# arduinosnull.net
KiCad netlist of a schematic drawn in EAGLE
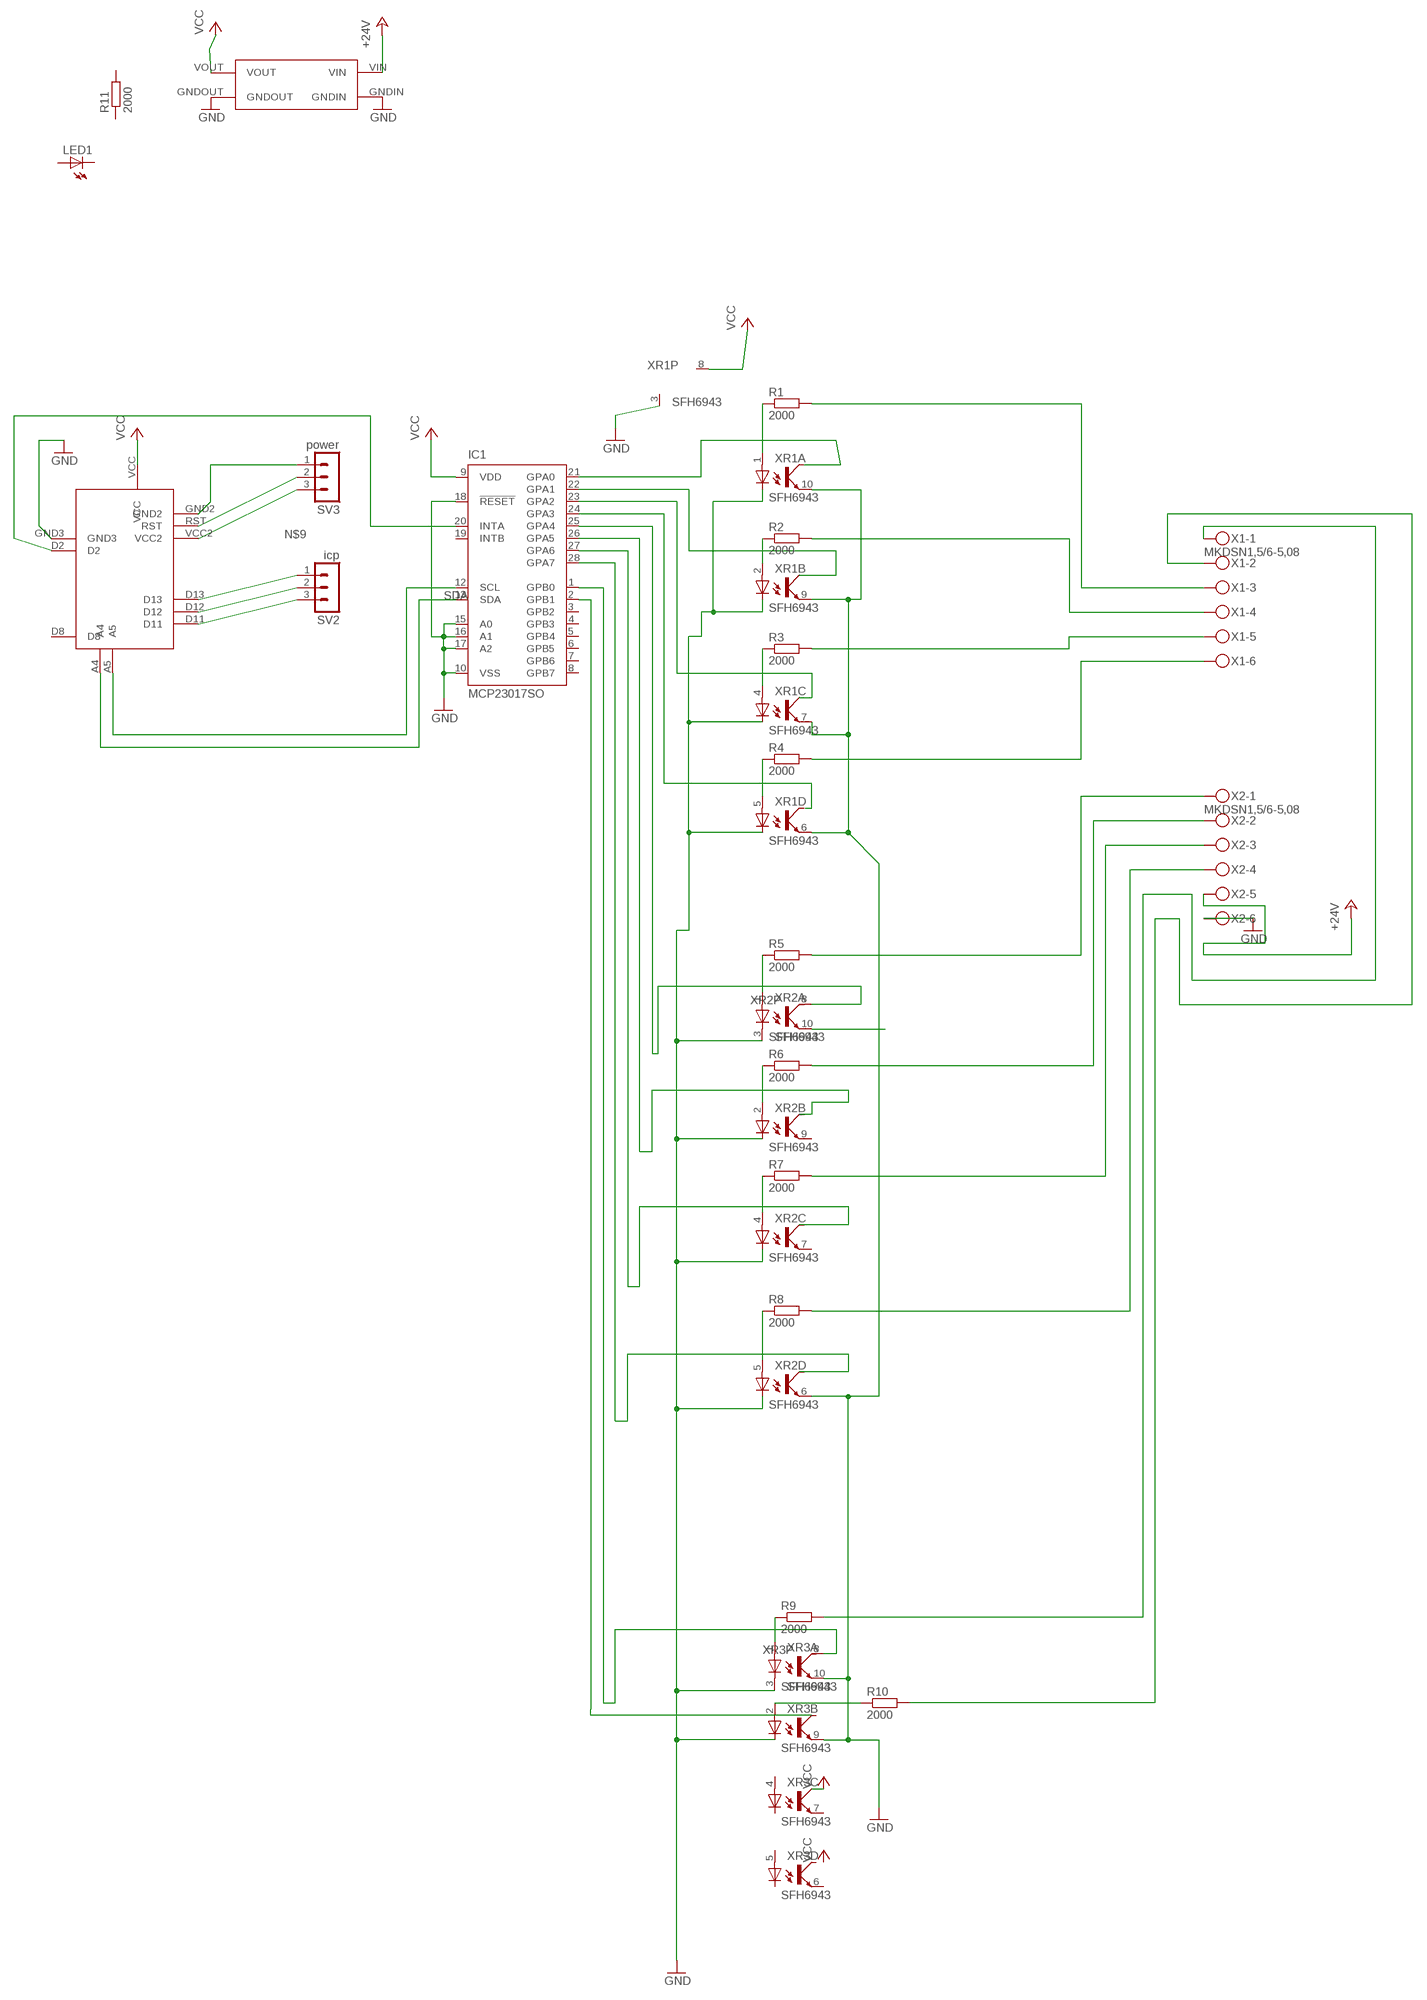
[diagram p0: schematic, sheet 1]

(export (version "E")
  (design (tool "Eeschema 10.0.6"))
  (components
    (comp (ref "IC1")
      (value "MCP23017SO")
      (footprint "eagle-import:SO28W")
      (fields (field (name "MF") "MICROCHIP") (field (name "MPN") "MCP23017-E/SO"))
      (libsource (lib "eagle-import") (part "MCP23017SO"))
    )
    (comp (ref "LED1")
      (value "LEDSML0805")
      (footprint "eagle-import:SML0805")
      (libsource (lib "eagle-import") (part "LEDSML0805"))
    )
    (comp (ref "R1")
      (value "2000")
      (footprint "eagle-import:M0805")
      (libsource (lib "eagle-import") (part "R-EU_M0805"))
    )
    (comp (ref "R2")
      (value "2000")
      (footprint "eagle-import:M0805")
      (libsource (lib "eagle-import") (part "R-EU_M0805"))
    )
    (comp (ref "R3")
      (value "2000")
      (footprint "eagle-import:M0805")
      (libsource (lib "eagle-import") (part "R-EU_M0805"))
    )
    (comp (ref "R4")
      (value "2000")
      (footprint "eagle-import:M0805")
      (libsource (lib "eagle-import") (part "R-EU_M0805"))
    )
    (comp (ref "R5")
      (value "2000")
      (footprint "eagle-import:M0805")
      (libsource (lib "eagle-import") (part "R-EU_M0805"))
    )
    (comp (ref "R6")
      (value "2000")
      (footprint "eagle-import:M0805")
      (libsource (lib "eagle-import") (part "R-EU_M0805"))
    )
    (comp (ref "R7")
      (value "2000")
      (footprint "eagle-import:M0805")
      (libsource (lib "eagle-import") (part "R-EU_M0805"))
    )
    (comp (ref "R8")
      (value "2000")
      (footprint "eagle-import:M0805")
      (libsource (lib "eagle-import") (part "R-EU_M0805"))
    )
    (comp (ref "R9")
      (value "2000")
      (footprint "eagle-import:M0805")
      (libsource (lib "eagle-import") (part "R-EU_M0805"))
    )
    (comp (ref "R10")
      (value "2000")
      (footprint "eagle-import:M0805")
      (libsource (lib "eagle-import") (part "R-EU_M0805"))
    )
    (comp (ref "R11")
      (value "2000")
      (footprint "eagle-import:M0805")
      (libsource (lib "eagle-import") (part "R-EU_M0805"))
    )
    (comp (ref "SV2")
      (value "icp")
      (footprint "eagle-import:MA03-1")
      (libsource (lib "eagle-import") (part "MA03-1"))
    )
    (comp (ref "SV3")
      (value "power")
      (footprint "eagle-import:MA03-1")
      (libsource (lib "eagle-import") (part "MA03-1"))
    )
    (comp (ref "U$1")
      (value "ARDUINOPROMINIREDUCED")
      (footprint "eagle-import:ARDUINOPROMINIREDUCED")
      (libsource (lib "eagle-import") (part "ARDUINOPROMINIREDUCED"))
    )
    (comp (ref "U$2")
      (value "VREGMODULE")
      (footprint "eagle-import:VREGMODULE")
      (libsource (lib "eagle-import") (part "VREGMODULE"))
    )
    (comp (ref "X1")
      (value "MKDSN1,5/6-5,08")
      (footprint "eagle-import:MKDSN1,5_6-5,08")
      (libsource (lib "eagle-import") (part "MKDSN1,5/6-5,08"))
    )
    (comp (ref "X2")
      (value "MKDSN1,5/6-5,08")
      (footprint "eagle-import:MKDSN1,5_6-5,08")
      (libsource (lib "eagle-import") (part "MKDSN1,5/6-5,08"))
    )
    (comp (ref "XR1")
      (value "SFH6943")
      (footprint "eagle-import:SOT223_10")
      (fields (field (name "MPN") "SFH6943A-4T"))
      (libsource (lib "eagle-import") (part "SFH6943"))
    )
    (comp (ref "XR2")
      (value "SFH6943")
      (footprint "eagle-import:SOT223_10")
      (fields (field (name "MPN") "SFH6943A-4T"))
      (libsource (lib "eagle-import") (part "SFH6943"))
    )
    (comp (ref "XR3")
      (value "SFH6943")
      (footprint "eagle-import:SOT223_10")
      (fields (field (name "MPN") "SFH6943A-4T"))
      (libsource (lib "eagle-import") (part "SFH6943"))
    )
  )
  (nets
    (net (code "1") (name "+24V") (class "Default")
      (node (ref "U$2") (pin "VIN") (pinfunction "VIN_VIN") (pintype "bidirectional"))
      (node (ref "X2") (pin "5") (pinfunction "KL_5") (pintype "passive"))
    )
    (net (code "2") (name "/N$9") (class "Default")
      (node (ref "SV3") (pin "3") (pinfunction "3_3") (pintype "passive"))
      (node (ref "U$1") (pin "VCC2") (pinfunction "VCC2_VCC2") (pintype "bidirectional"))
    )
    (net (code "3") (name "/SDA") (class "Default")
      (node (ref "IC1") (pin "13") (pinfunction "SDA_13") (pintype "bidirectional"))
      (node (ref "U$1") (pin "A4") (pinfunction "A4_A4") (pintype "bidirectional"))
    )
    (net (code "4") (name "GND") (class "Default")
      (node (ref "IC1") (pin "10") (pinfunction "VSS_10") (pintype "power_in"))
      (node (ref "IC1") (pin "15") (pinfunction "A0_15") (pintype "input"))
      (node (ref "IC1") (pin "16") (pinfunction "A1_16") (pintype "input"))
      (node (ref "IC1") (pin "17") (pinfunction "A2_17") (pintype "input"))
      (node (ref "IC1") (pin "18") (pinfunction "~{RESET}_18") (pintype "input"))
      (node (ref "U$1") (pin "GND3") (pinfunction "GND3_GND3") (pintype "bidirectional"))
      (node (ref "U$2") (pin "GNDIN") (pinfunction "GNDIN_GNDIN") (pintype "bidirectional"))
      (node (ref "U$2") (pin "GNDOUT") (pinfunction "GNDOUT_GNDOUT") (pintype "bidirectional"))
      (node (ref "X2") (pin "6") (pinfunction "KL_6") (pintype "passive"))
      (node (ref "XR1") (pin "10") (pinfunction "EMI_10") (pintype "passive"))
      (node (ref "XR1") (pin "3") (pinfunction "COM-CAT_3") (pintype "passive"))
      (node (ref "XR1") (pin "6") (pinfunction "EMI_6") (pintype "passive"))
      (node (ref "XR1") (pin "7") (pinfunction "EMI_7") (pintype "passive"))
      (node (ref "XR1") (pin "9") (pinfunction "EMI_9") (pintype "passive"))
      (node (ref "XR2") (pin "3") (pinfunction "COM-CAT_3") (pintype "passive"))
      (node (ref "XR2") (pin "6") (pinfunction "EMI_6") (pintype "passive"))
      (node (ref "XR3") (pin "10") (pinfunction "EMI_10") (pintype "passive"))
      (node (ref "XR3") (pin "3") (pinfunction "COM-CAT_3") (pintype "passive"))
      (node (ref "XR3") (pin "9") (pinfunction "EMI_9") (pintype "passive"))
    )
    (net (code "5") (name "Net-(IC1-GPA4)") (class "Default")
      (node (ref "IC1") (pin "25") (pinfunction "GPA4_25") (pintype "bidirectional"))
      (node (ref "XR2") (pin "8") (pinfunction "COM-COL_8") (pintype "passive"))
    )
    (net (code "6") (name "Net-(IC1-GPB0)") (class "Default")
      (node (ref "IC1") (pin "1") (pinfunction "GPB0_1") (pintype "bidirectional"))
      (node (ref "XR3") (pin "8") (pinfunction "COM-COL_8") (pintype "passive"))
    )
    (net (code "7") (name "Net-(IC1-INTA)") (class "Default")
      (node (ref "IC1") (pin "20") (pinfunction "INTA_20") (pintype "output"))
      (node (ref "U$1") (pin "D2") (pinfunction "D2_D2") (pintype "bidirectional"))
    )
    (net (code "8") (name "Net-(IC1-SCL)") (class "Default")
      (node (ref "IC1") (pin "12") (pinfunction "SCL_12") (pintype "input"))
      (node (ref "U$1") (pin "A5") (pinfunction "A5_A5") (pintype "bidirectional"))
    )
    (net (code "9") (name "Net-(SV2-Pad1)") (class "Default")
      (node (ref "SV2") (pin "1") (pinfunction "1_1") (pintype "passive"))
      (node (ref "U$1") (pin "D13") (pinfunction "D13_D13") (pintype "bidirectional"))
    )
    (net (code "10") (name "Net-(SV2-Pad2)") (class "Default")
      (node (ref "SV2") (pin "2") (pinfunction "2_2") (pintype "passive"))
      (node (ref "U$1") (pin "D12") (pinfunction "D12_D12") (pintype "bidirectional"))
    )
    (net (code "11") (name "Net-(SV2-Pad3)") (class "Default")
      (node (ref "SV2") (pin "3") (pinfunction "3_3") (pintype "passive"))
      (node (ref "U$1") (pin "D11") (pinfunction "D11_D11") (pintype "bidirectional"))
    )
    (net (code "12") (name "Net-(SV3-Pad1)") (class "Default")
      (node (ref "SV3") (pin "1") (pinfunction "1_1") (pintype "passive"))
      (node (ref "U$1") (pin "GND2") (pinfunction "GND2_GND2") (pintype "bidirectional"))
    )
    (net (code "13") (name "Net-(SV3-Pad2)") (class "Default")
      (node (ref "SV3") (pin "2") (pinfunction "2_2") (pintype "passive"))
      (node (ref "U$1") (pin "RST") (pinfunction "RST_RST") (pintype "bidirectional"))
    )
    (net (code "14") (name "Net-(X1A-KL)") (class "Default")
      (node (ref "R9") (pin "2") (pinfunction "2_2") (pintype "passive"))
      (node (ref "X1") (pin "1") (pinfunction "KL_1") (pintype "passive"))
    )
    (net (code "15") (name "Net-(X1B-KL)") (class "Default")
      (node (ref "R10") (pin "2") (pinfunction "2_2") (pintype "passive"))
      (node (ref "X1") (pin "2") (pinfunction "KL_2") (pintype "passive"))
    )
    (net (code "16") (name "Net-(X1C-KL)") (class "Default")
      (node (ref "R1") (pin "2") (pinfunction "2_2") (pintype "passive"))
      (node (ref "X1") (pin "3") (pinfunction "KL_3") (pintype "passive"))
    )
    (net (code "17") (name "Net-(X1D-KL)") (class "Default")
      (node (ref "R2") (pin "2") (pinfunction "2_2") (pintype "passive"))
      (node (ref "X1") (pin "4") (pinfunction "KL_4") (pintype "passive"))
    )
    (net (code "18") (name "Net-(X1E-KL)") (class "Default")
      (node (ref "R3") (pin "2") (pinfunction "2_2") (pintype "passive"))
      (node (ref "X1") (pin "5") (pinfunction "KL_5") (pintype "passive"))
    )
    (net (code "19") (name "Net-(X1F-KL)") (class "Default")
      (node (ref "R4") (pin "2") (pinfunction "2_2") (pintype "passive"))
      (node (ref "X1") (pin "6") (pinfunction "KL_6") (pintype "passive"))
    )
    (net (code "20") (name "Net-(X2A-KL)") (class "Default")
      (node (ref "R5") (pin "2") (pinfunction "2_2") (pintype "passive"))
      (node (ref "X2") (pin "1") (pinfunction "KL_1") (pintype "passive"))
    )
    (net (code "21") (name "Net-(X2B-KL)") (class "Default")
      (node (ref "R6") (pin "2") (pinfunction "2_2") (pintype "passive"))
      (node (ref "X2") (pin "2") (pinfunction "KL_2") (pintype "passive"))
    )
    (net (code "22") (name "Net-(X2C-KL)") (class "Default")
      (node (ref "R7") (pin "2") (pinfunction "2_2") (pintype "passive"))
      (node (ref "X2") (pin "3") (pinfunction "KL_3") (pintype "passive"))
    )
    (net (code "23") (name "Net-(X2D-KL)") (class "Default")
      (node (ref "R8") (pin "2") (pinfunction "2_2") (pintype "passive"))
      (node (ref "X2") (pin "4") (pinfunction "KL_4") (pintype "passive"))
    )
    (net (code "24") (name "Net-(XR1A-A)") (class "Default")
      (node (ref "R1") (pin "1") (pinfunction "1_1") (pintype "passive"))
      (node (ref "XR1") (pin "1") (pinfunction "A_1") (pintype "passive"))
    )
    (net (code "25") (name "Net-(XR1B-A)") (class "Default")
      (node (ref "R2") (pin "1") (pinfunction "1_1") (pintype "passive"))
      (node (ref "XR1") (pin "2") (pinfunction "A_2") (pintype "passive"))
    )
    (net (code "26") (name "Net-(XR1C-A)") (class "Default")
      (node (ref "R3") (pin "1") (pinfunction "1_1") (pintype "passive"))
      (node (ref "XR1") (pin "4") (pinfunction "A_4") (pintype "passive"))
    )
    (net (code "27") (name "Net-(XR1D-A)") (class "Default")
      (node (ref "R4") (pin "1") (pinfunction "1_1") (pintype "passive"))
      (node (ref "XR1") (pin "5") (pinfunction "A_5") (pintype "passive"))
    )
    (net (code "28") (name "Net-(XR2A-A)") (class "Default")
      (node (ref "R5") (pin "1") (pinfunction "1_1") (pintype "passive"))
      (node (ref "XR2") (pin "1") (pinfunction "A_1") (pintype "passive"))
    )
    (net (code "29") (name "Net-(XR2B-A)") (class "Default")
      (node (ref "R6") (pin "1") (pinfunction "1_1") (pintype "passive"))
      (node (ref "XR2") (pin "2") (pinfunction "A_2") (pintype "passive"))
    )
    (net (code "30") (name "Net-(XR2C-A)") (class "Default")
      (node (ref "R7") (pin "1") (pinfunction "1_1") (pintype "passive"))
      (node (ref "XR2") (pin "4") (pinfunction "A_4") (pintype "passive"))
    )
    (net (code "31") (name "Net-(XR2D-A)") (class "Default")
      (node (ref "R8") (pin "1") (pinfunction "1_1") (pintype "passive"))
      (node (ref "XR2") (pin "5") (pinfunction "A_5") (pintype "passive"))
    )
    (net (code "32") (name "Net-(XR3A-A)") (class "Default")
      (node (ref "R9") (pin "1") (pinfunction "1_1") (pintype "passive"))
      (node (ref "XR3") (pin "1") (pinfunction "A_1") (pintype "passive"))
    )
    (net (code "33") (name "Net-(XR3B-A)") (class "Default")
      (node (ref "R10") (pin "1") (pinfunction "1_1") (pintype "passive"))
      (node (ref "XR3") (pin "2") (pinfunction "A_2") (pintype "passive"))
    )
    (net (code "34") (name "VCC") (class "Default")
      (node (ref "IC1") (pin "9") (pinfunction "VDD_9") (pintype "power_in"))
      (node (ref "U$1") (pin "VCC") (pinfunction "VCC_VCC") (pintype "bidirectional"))
      (node (ref "U$2") (pin "VOUT") (pinfunction "VOUT_VOUT") (pintype "bidirectional"))
      (node (ref "XR1") (pin "8") (pinfunction "COM-COL_8") (pintype "passive"))
    )
    (net (code "35") (name "unconnected-(IC1-GPA0-Pad21)") (class "Default")
      (node (ref "IC1") (pin "21") (pinfunction "GPA0_21") (pintype "bidirectional"))
    )
    (net (code "36") (name "unconnected-(IC1-GPA1-Pad22)") (class "Default")
      (node (ref "IC1") (pin "22") (pinfunction "GPA1_22") (pintype "bidirectional"))
    )
    (net (code "37") (name "unconnected-(IC1-GPA2-Pad23)") (class "Default")
      (node (ref "IC1") (pin "23") (pinfunction "GPA2_23") (pintype "bidirectional"))
    )
    (net (code "38") (name "unconnected-(IC1-GPA3-Pad24)") (class "Default")
      (node (ref "IC1") (pin "24") (pinfunction "GPA3_24") (pintype "bidirectional"))
    )
    (net (code "39") (name "unconnected-(IC1-GPA5-Pad26)") (class "Default")
      (node (ref "IC1") (pin "26") (pinfunction "GPA5_26") (pintype "bidirectional"))
    )
    (net (code "40") (name "unconnected-(IC1-GPA6-Pad27)") (class "Default")
      (node (ref "IC1") (pin "27") (pinfunction "GPA6_27") (pintype "bidirectional"))
    )
    (net (code "41") (name "unconnected-(IC1-GPA7-Pad28)") (class "Default")
      (node (ref "IC1") (pin "28") (pinfunction "GPA7_28") (pintype "bidirectional"))
    )
    (net (code "42") (name "unconnected-(IC1-GPB1-Pad2)") (class "Default")
      (node (ref "IC1") (pin "2") (pinfunction "GPB1_2") (pintype "bidirectional"))
    )
    (net (code "43") (name "unconnected-(IC1-GPB2-Pad3)") (class "Default")
      (node (ref "IC1") (pin "3") (pinfunction "GPB2_3") (pintype "bidirectional"))
    )
    (net (code "44") (name "unconnected-(IC1-GPB3-Pad4)") (class "Default")
      (node (ref "IC1") (pin "4") (pinfunction "GPB3_4") (pintype "bidirectional"))
    )
    (net (code "45") (name "unconnected-(IC1-GPB4-Pad5)") (class "Default")
      (node (ref "IC1") (pin "5") (pinfunction "GPB4_5") (pintype "bidirectional"))
    )
    (net (code "46") (name "unconnected-(IC1-GPB5-Pad6)") (class "Default")
      (node (ref "IC1") (pin "6") (pinfunction "GPB5_6") (pintype "bidirectional"))
    )
    (net (code "47") (name "unconnected-(IC1-GPB6-Pad7)") (class "Default")
      (node (ref "IC1") (pin "7") (pinfunction "GPB6_7") (pintype "bidirectional"))
    )
    (net (code "48") (name "unconnected-(IC1-GPB7-Pad8)") (class "Default")
      (node (ref "IC1") (pin "8") (pinfunction "GPB7_8") (pintype "bidirectional"))
    )
    (net (code "49") (name "unconnected-(IC1-INTB-Pad19)") (class "Default")
      (node (ref "IC1") (pin "19") (pinfunction "INTB_19") (pintype "output"))
    )
    (net (code "50") (name "unconnected-(LED1-PadA)") (class "Default")
      (node (ref "LED1") (pin "A") (pinfunction "A_A") (pintype "passive"))
    )
    (net (code "51") (name "unconnected-(LED1-PadC)") (class "Default")
      (node (ref "LED1") (pin "C") (pinfunction "C_C") (pintype "passive"))
    )
    (net (code "52") (name "unconnected-(R11-Pad1)") (class "Default")
      (node (ref "R11") (pin "1") (pinfunction "1_1") (pintype "passive"))
    )
    (net (code "53") (name "unconnected-(R11-Pad2)") (class "Default")
      (node (ref "R11") (pin "2") (pinfunction "2_2") (pintype "passive"))
    )
    (net (code "54") (name "unconnected-(U$1-PadD8)") (class "Default")
      (node (ref "U$1") (pin "D8") (pinfunction "D8_D8") (pintype "bidirectional"))
    )
    (net (code "55") (name "unconnected-(XR2A-EMI-Pad10)") (class "Default")
      (node (ref "XR2") (pin "10") (pinfunction "EMI_10") (pintype "passive"))
    )
    (net (code "56") (name "unconnected-(XR2B-EMI-Pad9)") (class "Default")
      (node (ref "XR2") (pin "9") (pinfunction "EMI_9") (pintype "passive"))
    )
    (net (code "57") (name "unconnected-(XR2C-EMI-Pad7)") (class "Default")
      (node (ref "XR2") (pin "7") (pinfunction "EMI_7") (pintype "passive"))
    )
    (net (code "58") (name "unconnected-(XR3C-A-Pad4)") (class "Default")
      (node (ref "XR3") (pin "4") (pinfunction "A_4") (pintype "passive"))
    )
    (net (code "59") (name "unconnected-(XR3C-EMI-Pad7)") (class "Default")
      (node (ref "XR3") (pin "7") (pinfunction "EMI_7") (pintype "passive"))
    )
    (net (code "60") (name "unconnected-(XR3D-A-Pad5)") (class "Default")
      (node (ref "XR3") (pin "5") (pinfunction "A_5") (pintype "passive"))
    )
    (net (code "61") (name "unconnected-(XR3D-EMI-Pad6)") (class "Default")
      (node (ref "XR3") (pin "6") (pinfunction "EMI_6") (pintype "passive"))
    )
  )
)
